# links_v40.net
KiCad netlist of a schematic drawn in EAGLE
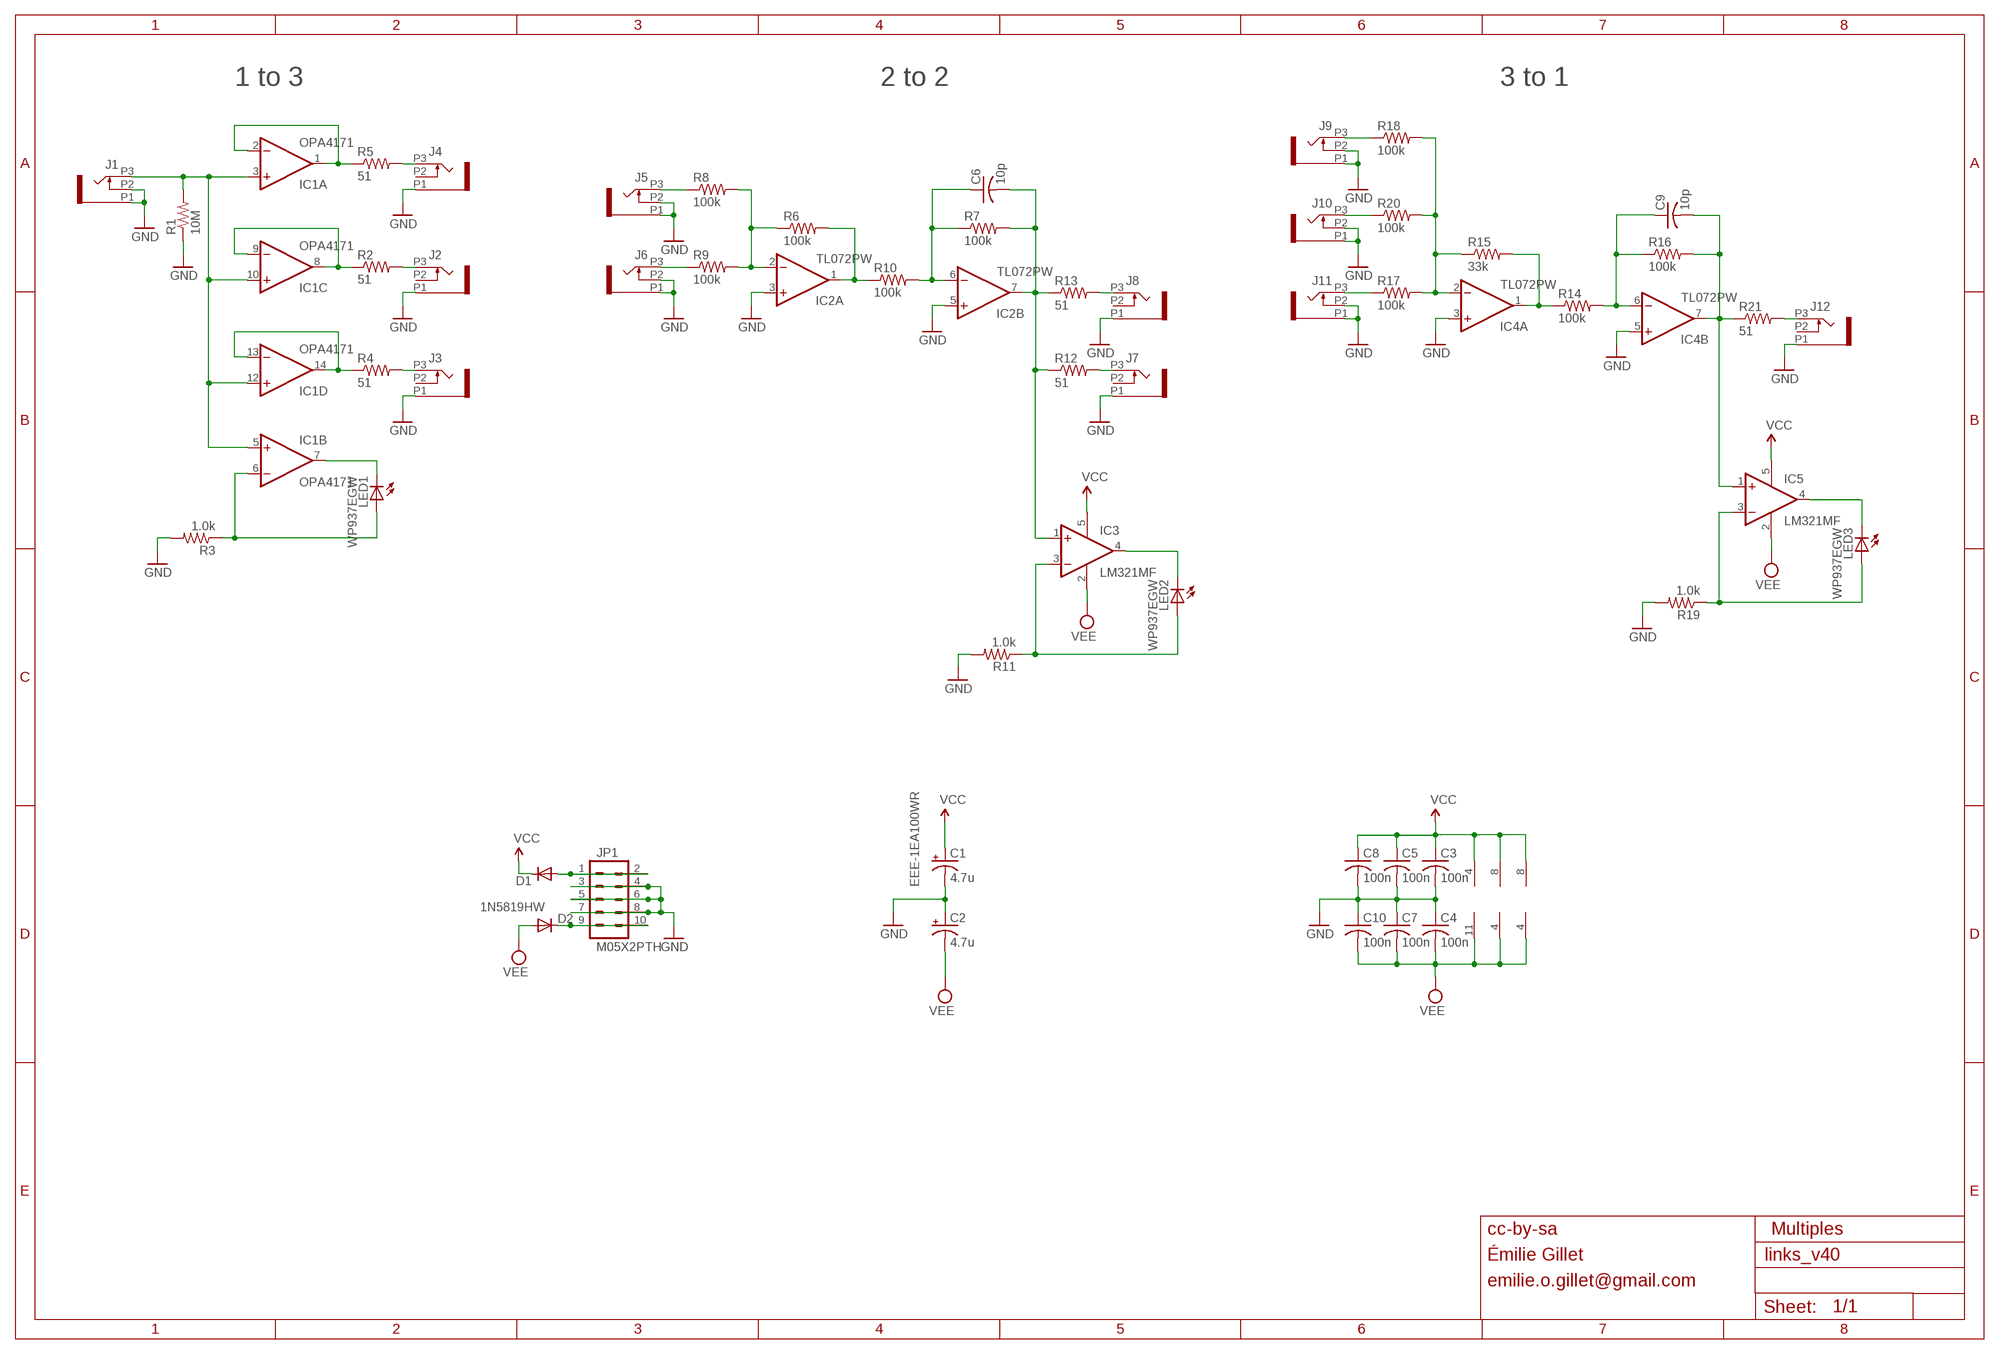
[diagram p0: schematic, sheet 1]

(export (version "E")
  (design (tool "Eeschema 10.0.6"))
  (components
    (comp (ref "C1")
      (value "4.7u")
      (footprint "eagle-import:PANASONIC_A")
      (libsource (lib "eagle-import") (part "CPOL-USA"))
    )
    (comp (ref "C2")
      (value "4.7u")
      (footprint "eagle-import:PANASONIC_A")
      (libsource (lib "eagle-import") (part "CPOL-USA"))
    )
    (comp (ref "C3")
      (value "100n")
      (footprint "eagle-import:C0603")
      (libsource (lib "eagle-import") (part "C-USC0603"))
    )
    (comp (ref "C4")
      (value "100n")
      (footprint "eagle-import:C0603")
      (libsource (lib "eagle-import") (part "C-USC0603"))
    )
    (comp (ref "C5")
      (value "100n")
      (footprint "eagle-import:C0603")
      (libsource (lib "eagle-import") (part "C-USC0603"))
    )
    (comp (ref "C6")
      (value "10p")
      (footprint "eagle-import:C0603")
      (libsource (lib "eagle-import") (part "C-USC0603"))
    )
    (comp (ref "C7")
      (value "100n")
      (footprint "eagle-import:C0603")
      (libsource (lib "eagle-import") (part "C-USC0603"))
    )
    (comp (ref "C8")
      (value "100n")
      (footprint "eagle-import:C0603")
      (libsource (lib "eagle-import") (part "C-USC0603"))
    )
    (comp (ref "C9")
      (value "10p")
      (footprint "eagle-import:C0603")
      (libsource (lib "eagle-import") (part "C-USC0603"))
    )
    (comp (ref "C10")
      (value "100n")
      (footprint "eagle-import:C0603")
      (libsource (lib "eagle-import") (part "C-USC0603"))
    )
    (comp (ref "D1")
      (value "1N5819HW")
      (footprint "eagle-import:SOD123")
      (libsource (lib "eagle-import") (part "DIODE-SOD123"))
    )
    (comp (ref "D2")
      (value "1N5819HW")
      (footprint "eagle-import:SOD123")
      (libsource (lib "eagle-import") (part "DIODE-SOD123"))
    )
    (comp (ref "IC1")
      (value "OPA4171")
      (footprint "eagle-import:TSSOP14")
      (libsource (lib "eagle-import") (part "TL074PW"))
    )
    (comp (ref "IC2")
      (value "TL072PW")
      (footprint "eagle-import:TSSOP8")
      (libsource (lib "eagle-import") (part "TL072PW"))
    )
    (comp (ref "IC3")
      (value "LM321MF")
      (footprint "eagle-import:SOT23-5")
      (libsource (lib "eagle-import") (part "LM321?MF"))
    )
    (comp (ref "IC4")
      (value "TL072PW")
      (footprint "eagle-import:TSSOP8")
      (libsource (lib "eagle-import") (part "TL072PW"))
    )
    (comp (ref "IC5")
      (value "LM321MF")
      (footprint "eagle-import:SOT23-5")
      (libsource (lib "eagle-import") (part "LM321?MF"))
    )
    (comp (ref "J1")
      (value "PJ301_THONKICONN6")
      (footprint "eagle-import:WQP_PJ_301M6")
      (libsource (lib "eagle-import") (part "PJ301_THONKICONN6"))
    )
    (comp (ref "J2")
      (value "PJ301_THONKICONN6")
      (footprint "eagle-import:WQP_PJ_301M6")
      (libsource (lib "eagle-import") (part "PJ301_THONKICONN6"))
    )
    (comp (ref "J3")
      (value "PJ301_THONKICONN6")
      (footprint "eagle-import:WQP_PJ_301M6")
      (libsource (lib "eagle-import") (part "PJ301_THONKICONN6"))
    )
    (comp (ref "J4")
      (value "PJ301_THONKICONN6")
      (footprint "eagle-import:WQP_PJ_301M6")
      (libsource (lib "eagle-import") (part "PJ301_THONKICONN6"))
    )
    (comp (ref "J5")
      (value "PJ301_THONKICONN6")
      (footprint "eagle-import:WQP_PJ_301M6")
      (libsource (lib "eagle-import") (part "PJ301_THONKICONN6"))
    )
    (comp (ref "J6")
      (value "PJ301_THONKICONN6")
      (footprint "eagle-import:WQP_PJ_301M6")
      (libsource (lib "eagle-import") (part "PJ301_THONKICONN6"))
    )
    (comp (ref "J7")
      (value "PJ301_THONKICONN6")
      (footprint "eagle-import:WQP_PJ_301M6")
      (libsource (lib "eagle-import") (part "PJ301_THONKICONN6"))
    )
    (comp (ref "J8")
      (value "PJ301_THONKICONN6")
      (footprint "eagle-import:WQP_PJ_301M6")
      (libsource (lib "eagle-import") (part "PJ301_THONKICONN6"))
    )
    (comp (ref "J9")
      (value "PJ301_THONKICONN6")
      (footprint "eagle-import:WQP_PJ_301M6")
      (libsource (lib "eagle-import") (part "PJ301_THONKICONN6"))
    )
    (comp (ref "J10")
      (value "PJ301_THONKICONN6")
      (footprint "eagle-import:WQP_PJ_301M6")
      (libsource (lib "eagle-import") (part "PJ301_THONKICONN6"))
    )
    (comp (ref "J11")
      (value "PJ301_THONKICONN6")
      (footprint "eagle-import:WQP_PJ_301M6")
      (libsource (lib "eagle-import") (part "PJ301_THONKICONN6"))
    )
    (comp (ref "J12")
      (value "PJ301_THONKICONN6")
      (footprint "eagle-import:WQP_PJ_301M6")
      (libsource (lib "eagle-import") (part "PJ301_THONKICONN6"))
    )
    (comp (ref "JP1")
      (value "M05X2PTH")
      (footprint "eagle-import:AVR_ICSP")
      (libsource (lib "eagle-import") (part "M05X2PTH"))
    )
    (comp (ref "LED1")
      (value "WP937EGW")
      (footprint "eagle-import:LED3MM")
      (libsource (lib "eagle-import") (part "LED3MM"))
    )
    (comp (ref "LED2")
      (value "WP937EGW")
      (footprint "eagle-import:LED3MM")
      (libsource (lib "eagle-import") (part "LED3MM"))
    )
    (comp (ref "LED3")
      (value "WP937EGW")
      (footprint "eagle-import:LED3MM")
      (libsource (lib "eagle-import") (part "LED3MM"))
    )
    (comp (ref "R1")
      (value "10M")
      (footprint "eagle-import:R0603")
      (libsource (lib "eagle-import") (part "R-US_R0603"))
    )
    (comp (ref "R2")
      (value "51")
      (footprint "eagle-import:R0603")
      (libsource (lib "eagle-import") (part "R-US_R0603"))
    )
    (comp (ref "R3")
      (value "1.0k")
      (footprint "eagle-import:R0603")
      (libsource (lib "eagle-import") (part "R-US_R0603"))
    )
    (comp (ref "R4")
      (value "51")
      (footprint "eagle-import:R0603")
      (libsource (lib "eagle-import") (part "R-US_R0603"))
    )
    (comp (ref "R5")
      (value "51")
      (footprint "eagle-import:R0603")
      (libsource (lib "eagle-import") (part "R-US_R0603"))
    )
    (comp (ref "R6")
      (value "100k")
      (footprint "eagle-import:R0603")
      (libsource (lib "eagle-import") (part "R-US_R0603"))
    )
    (comp (ref "R7")
      (value "100k")
      (footprint "eagle-import:R0603")
      (libsource (lib "eagle-import") (part "R-US_R0603"))
    )
    (comp (ref "R8")
      (value "100k")
      (footprint "eagle-import:R0603")
      (libsource (lib "eagle-import") (part "R-US_R0603"))
    )
    (comp (ref "R9")
      (value "100k")
      (footprint "eagle-import:R0603")
      (libsource (lib "eagle-import") (part "R-US_R0603"))
    )
    (comp (ref "R10")
      (value "100k")
      (footprint "eagle-import:R0603")
      (libsource (lib "eagle-import") (part "R-US_R0603"))
    )
    (comp (ref "R11")
      (value "1.0k")
      (footprint "eagle-import:R0603")
      (libsource (lib "eagle-import") (part "R-US_R0603"))
    )
    (comp (ref "R12")
      (value "51")
      (footprint "eagle-import:R0603")
      (libsource (lib "eagle-import") (part "R-US_R0603"))
    )
    (comp (ref "R13")
      (value "51")
      (footprint "eagle-import:R0603")
      (libsource (lib "eagle-import") (part "R-US_R0603"))
    )
    (comp (ref "R14")
      (value "100k")
      (footprint "eagle-import:R0603")
      (libsource (lib "eagle-import") (part "R-US_R0603"))
    )
    (comp (ref "R15")
      (value "33k")
      (footprint "eagle-import:R0603")
      (libsource (lib "eagle-import") (part "R-US_R0603"))
    )
    (comp (ref "R16")
      (value "100k")
      (footprint "eagle-import:R0603")
      (libsource (lib "eagle-import") (part "R-US_R0603"))
    )
    (comp (ref "R17")
      (value "100k")
      (footprint "eagle-import:R0603")
      (libsource (lib "eagle-import") (part "R-US_R0603"))
    )
    (comp (ref "R18")
      (value "100k")
      (footprint "eagle-import:R0603")
      (libsource (lib "eagle-import") (part "R-US_R0603"))
    )
    (comp (ref "R19")
      (value "1.0k")
      (footprint "eagle-import:R0603")
      (libsource (lib "eagle-import") (part "R-US_R0603"))
    )
    (comp (ref "R20")
      (value "100k")
      (footprint "eagle-import:R0603")
      (libsource (lib "eagle-import") (part "R-US_R0603"))
    )
    (comp (ref "R21")
      (value "51")
      (footprint "eagle-import:R0603")
      (libsource (lib "eagle-import") (part "R-US_R0603"))
    )
  )
  (nets
    (net (code "1") (name "GND") (class "Default")
      (node (ref "C1") (pin "-") (pinfunction "-_-") (pintype "passive"))
      (node (ref "C10") (pin "1") (pinfunction "1_1") (pintype "passive"))
      (node (ref "C2") (pin "+") (pinfunction "+_+") (pintype "passive"))
      (node (ref "C3") (pin "2") (pinfunction "2_2") (pintype "passive"))
      (node (ref "C4") (pin "1") (pinfunction "1_1") (pintype "passive"))
      (node (ref "C5") (pin "2") (pinfunction "2_2") (pintype "passive"))
      (node (ref "C7") (pin "1") (pinfunction "1_1") (pintype "passive"))
      (node (ref "C8") (pin "2") (pinfunction "2_2") (pintype "passive"))
      (node (ref "IC2") (pin "3") (pinfunction "+IN_3") (pintype "input"))
      (node (ref "IC2") (pin "5") (pinfunction "+IN_5") (pintype "input"))
      (node (ref "IC4") (pin "3") (pinfunction "+IN_3") (pintype "input"))
      (node (ref "IC4") (pin "5") (pinfunction "+IN_5") (pintype "input"))
      (node (ref "J1") (pin "P1") (pinfunction "1_P1") (pintype "passive"))
      (node (ref "J1") (pin "P2") (pinfunction "2_P2") (pintype "passive"))
      (node (ref "J10") (pin "P1") (pinfunction "1_P1") (pintype "passive"))
      (node (ref "J10") (pin "P2") (pinfunction "2_P2") (pintype "passive"))
      (node (ref "J11") (pin "P1") (pinfunction "1_P1") (pintype "passive"))
      (node (ref "J11") (pin "P2") (pinfunction "2_P2") (pintype "passive"))
      (node (ref "J12") (pin "P1") (pinfunction "1_P1") (pintype "passive"))
      (node (ref "J2") (pin "P1") (pinfunction "1_P1") (pintype "passive"))
      (node (ref "J3") (pin "P1") (pinfunction "1_P1") (pintype "passive"))
      (node (ref "J4") (pin "P1") (pinfunction "1_P1") (pintype "passive"))
      (node (ref "J5") (pin "P1") (pinfunction "1_P1") (pintype "passive"))
      (node (ref "J5") (pin "P2") (pinfunction "2_P2") (pintype "passive"))
      (node (ref "J6") (pin "P1") (pinfunction "1_P1") (pintype "passive"))
      (node (ref "J6") (pin "P2") (pinfunction "2_P2") (pintype "passive"))
      (node (ref "J7") (pin "P1") (pinfunction "1_P1") (pintype "passive"))
      (node (ref "J8") (pin "P1") (pinfunction "1_P1") (pintype "passive"))
      (node (ref "J9") (pin "P1") (pinfunction "1_P1") (pintype "passive"))
      (node (ref "J9") (pin "P2") (pinfunction "2_P2") (pintype "passive"))
      (node (ref "JP1") (pin "3") (pinfunction "3_3") (pintype "passive"))
      (node (ref "JP1") (pin "4") (pinfunction "4_4") (pintype "passive"))
      (node (ref "JP1") (pin "5") (pinfunction "5_5") (pintype "passive"))
      (node (ref "JP1") (pin "6") (pinfunction "6_6") (pintype "passive"))
      (node (ref "JP1") (pin "7") (pinfunction "7_7") (pintype "passive"))
      (node (ref "JP1") (pin "8") (pinfunction "8_8") (pintype "passive"))
      (node (ref "R1") (pin "1") (pinfunction "1_1") (pintype "passive"))
      (node (ref "R11") (pin "2") (pinfunction "2_2") (pintype "passive"))
      (node (ref "R19") (pin "2") (pinfunction "2_2") (pintype "passive"))
      (node (ref "R3") (pin "2") (pinfunction "2_2") (pintype "passive"))
    )
    (net (code "2") (name "Net-(D1-PadA)") (class "Default")
      (node (ref "D1") (pin "A") (pinfunction "A_A") (pintype "passive"))
      (node (ref "JP1") (pin "1") (pinfunction "1_1") (pintype "passive"))
      (node (ref "JP1") (pin "2") (pinfunction "2_2") (pintype "passive"))
    )
    (net (code "3") (name "Net-(D2-PadC)") (class "Default")
      (node (ref "D2") (pin "C") (pinfunction "C_C") (pintype "passive"))
      (node (ref "JP1") (pin "10") (pinfunction "10_10") (pintype "passive"))
      (node (ref "JP1") (pin "9") (pinfunction "9_9") (pintype "passive"))
    )
    (net (code "4") (name "Net-(IC1A-+IN)") (class "Default")
      (node (ref "IC1") (pin "10") (pinfunction "+IN_10") (pintype "input"))
      (node (ref "IC1") (pin "12") (pinfunction "+IN_12") (pintype "input"))
      (node (ref "IC1") (pin "3") (pinfunction "+IN_3") (pintype "input"))
      (node (ref "IC1") (pin "5") (pinfunction "+IN_5") (pintype "input"))
      (node (ref "J1") (pin "P3") (pinfunction "3_P3") (pintype "passive"))
      (node (ref "R1") (pin "2") (pinfunction "2_2") (pintype "passive"))
    )
    (net (code "5") (name "Net-(IC1A--IN)") (class "Default")
      (node (ref "IC1") (pin "1") (pinfunction "OUT_1") (pintype "output"))
      (node (ref "IC1") (pin "2") (pinfunction "-IN_2") (pintype "input"))
      (node (ref "R5") (pin "1") (pinfunction "1_1") (pintype "passive"))
    )
    (net (code "6") (name "Net-(IC1B--IN)") (class "Default")
      (node (ref "IC1") (pin "6") (pinfunction "-IN_6") (pintype "input"))
      (node (ref "LED1") (pin "A") (pinfunction "A_A") (pintype "passive"))
      (node (ref "R3") (pin "1") (pinfunction "1_1") (pintype "passive"))
    )
    (net (code "7") (name "Net-(IC1B-OUT)") (class "Default")
      (node (ref "IC1") (pin "7") (pinfunction "OUT_7") (pintype "output"))
      (node (ref "LED1") (pin "K") (pinfunction "C_K") (pintype "passive"))
    )
    (net (code "8") (name "Net-(IC1C--IN)") (class "Default")
      (node (ref "IC1") (pin "8") (pinfunction "OUT_8") (pintype "output"))
      (node (ref "IC1") (pin "9") (pinfunction "-IN_9") (pintype "input"))
      (node (ref "R2") (pin "1") (pinfunction "1_1") (pintype "passive"))
    )
    (net (code "9") (name "Net-(IC1D--IN)") (class "Default")
      (node (ref "IC1") (pin "13") (pinfunction "-IN_13") (pintype "input"))
      (node (ref "IC1") (pin "14") (pinfunction "OUT_14") (pintype "output"))
      (node (ref "R4") (pin "1") (pinfunction "1_1") (pintype "passive"))
    )
    (net (code "10") (name "Net-(IC2A--IN)") (class "Default")
      (node (ref "IC2") (pin "2") (pinfunction "-IN_2") (pintype "input"))
      (node (ref "R6") (pin "1") (pinfunction "1_1") (pintype "passive"))
      (node (ref "R8") (pin "2") (pinfunction "2_2") (pintype "passive"))
      (node (ref "R9") (pin "2") (pinfunction "2_2") (pintype "passive"))
    )
    (net (code "11") (name "Net-(IC2A-OUT)") (class "Default")
      (node (ref "IC2") (pin "1") (pinfunction "OUT_1") (pintype "output"))
      (node (ref "R10") (pin "1") (pinfunction "1_1") (pintype "passive"))
      (node (ref "R6") (pin "2") (pinfunction "2_2") (pintype "passive"))
    )
    (net (code "12") (name "Net-(IC2B--IN)") (class "Default")
      (node (ref "C6") (pin "1") (pinfunction "1_1") (pintype "passive"))
      (node (ref "IC2") (pin "6") (pinfunction "-IN_6") (pintype "input"))
      (node (ref "R10") (pin "2") (pinfunction "2_2") (pintype "passive"))
      (node (ref "R7") (pin "1") (pinfunction "1_1") (pintype "passive"))
    )
    (net (code "13") (name "Net-(IC2B-OUT)") (class "Default")
      (node (ref "C6") (pin "2") (pinfunction "2_2") (pintype "passive"))
      (node (ref "IC2") (pin "7") (pinfunction "OUT_7") (pintype "output"))
      (node (ref "IC3") (pin "1") (pinfunction "+IN_1") (pintype "input"))
      (node (ref "R12") (pin "1") (pinfunction "1_1") (pintype "passive"))
      (node (ref "R13") (pin "1") (pinfunction "1_1") (pintype "passive"))
      (node (ref "R7") (pin "2") (pinfunction "2_2") (pintype "passive"))
    )
    (net (code "14") (name "Net-(IC3--IN)") (class "Default")
      (node (ref "IC3") (pin "3") (pinfunction "-IN_3") (pintype "input"))
      (node (ref "LED2") (pin "A") (pinfunction "A_A") (pintype "passive"))
      (node (ref "R11") (pin "1") (pinfunction "1_1") (pintype "passive"))
    )
    (net (code "15") (name "Net-(IC3-OUT)") (class "Default")
      (node (ref "IC3") (pin "4") (pinfunction "OUT_4") (pintype "output"))
      (node (ref "LED2") (pin "K") (pinfunction "C_K") (pintype "passive"))
    )
    (net (code "16") (name "Net-(IC4A--IN)") (class "Default")
      (node (ref "IC4") (pin "2") (pinfunction "-IN_2") (pintype "input"))
      (node (ref "R15") (pin "1") (pinfunction "1_1") (pintype "passive"))
      (node (ref "R17") (pin "2") (pinfunction "2_2") (pintype "passive"))
      (node (ref "R18") (pin "2") (pinfunction "2_2") (pintype "passive"))
      (node (ref "R20") (pin "2") (pinfunction "2_2") (pintype "passive"))
    )
    (net (code "17") (name "Net-(IC4A-OUT)") (class "Default")
      (node (ref "IC4") (pin "1") (pinfunction "OUT_1") (pintype "output"))
      (node (ref "R14") (pin "1") (pinfunction "1_1") (pintype "passive"))
      (node (ref "R15") (pin "2") (pinfunction "2_2") (pintype "passive"))
    )
    (net (code "18") (name "Net-(IC4B--IN)") (class "Default")
      (node (ref "C9") (pin "1") (pinfunction "1_1") (pintype "passive"))
      (node (ref "IC4") (pin "6") (pinfunction "-IN_6") (pintype "input"))
      (node (ref "R14") (pin "2") (pinfunction "2_2") (pintype "passive"))
      (node (ref "R16") (pin "1") (pinfunction "1_1") (pintype "passive"))
    )
    (net (code "19") (name "Net-(IC4B-OUT)") (class "Default")
      (node (ref "C9") (pin "2") (pinfunction "2_2") (pintype "passive"))
      (node (ref "IC4") (pin "7") (pinfunction "OUT_7") (pintype "output"))
      (node (ref "IC5") (pin "1") (pinfunction "+IN_1") (pintype "input"))
      (node (ref "R16") (pin "2") (pinfunction "2_2") (pintype "passive"))
      (node (ref "R21") (pin "1") (pinfunction "1_1") (pintype "passive"))
    )
    (net (code "20") (name "Net-(IC5--IN)") (class "Default")
      (node (ref "IC5") (pin "3") (pinfunction "-IN_3") (pintype "input"))
      (node (ref "LED3") (pin "A") (pinfunction "A_A") (pintype "passive"))
      (node (ref "R19") (pin "1") (pinfunction "1_1") (pintype "passive"))
    )
    (net (code "21") (name "Net-(IC5-OUT)") (class "Default")
      (node (ref "IC5") (pin "4") (pinfunction "OUT_4") (pintype "output"))
      (node (ref "LED3") (pin "K") (pinfunction "C_K") (pintype "passive"))
    )
    (net (code "22") (name "Net-(J2-3)") (class "Default")
      (node (ref "J2") (pin "P3") (pinfunction "3_P3") (pintype "passive"))
      (node (ref "R2") (pin "2") (pinfunction "2_2") (pintype "passive"))
    )
    (net (code "23") (name "Net-(J3-3)") (class "Default")
      (node (ref "J3") (pin "P3") (pinfunction "3_P3") (pintype "passive"))
      (node (ref "R4") (pin "2") (pinfunction "2_2") (pintype "passive"))
    )
    (net (code "24") (name "Net-(J4-3)") (class "Default")
      (node (ref "J4") (pin "P3") (pinfunction "3_P3") (pintype "passive"))
      (node (ref "R5") (pin "2") (pinfunction "2_2") (pintype "passive"))
    )
    (net (code "25") (name "Net-(J5-3)") (class "Default")
      (node (ref "J5") (pin "P3") (pinfunction "3_P3") (pintype "passive"))
      (node (ref "R8") (pin "1") (pinfunction "1_1") (pintype "passive"))
    )
    (net (code "26") (name "Net-(J6-3)") (class "Default")
      (node (ref "J6") (pin "P3") (pinfunction "3_P3") (pintype "passive"))
      (node (ref "R9") (pin "1") (pinfunction "1_1") (pintype "passive"))
    )
    (net (code "27") (name "Net-(J7-3)") (class "Default")
      (node (ref "J7") (pin "P3") (pinfunction "3_P3") (pintype "passive"))
      (node (ref "R12") (pin "2") (pinfunction "2_2") (pintype "passive"))
    )
    (net (code "28") (name "Net-(J8-3)") (class "Default")
      (node (ref "J8") (pin "P3") (pinfunction "3_P3") (pintype "passive"))
      (node (ref "R13") (pin "2") (pinfunction "2_2") (pintype "passive"))
    )
    (net (code "29") (name "Net-(J9-3)") (class "Default")
      (node (ref "J9") (pin "P3") (pinfunction "3_P3") (pintype "passive"))
      (node (ref "R18") (pin "1") (pinfunction "1_1") (pintype "passive"))
    )
    (net (code "30") (name "Net-(J10-3)") (class "Default")
      (node (ref "J10") (pin "P3") (pinfunction "3_P3") (pintype "passive"))
      (node (ref "R20") (pin "1") (pinfunction "1_1") (pintype "passive"))
    )
    (net (code "31") (name "Net-(J11-3)") (class "Default")
      (node (ref "J11") (pin "P3") (pinfunction "3_P3") (pintype "passive"))
      (node (ref "R17") (pin "1") (pinfunction "1_1") (pintype "passive"))
    )
    (net (code "32") (name "Net-(J12-3)") (class "Default")
      (node (ref "J12") (pin "P3") (pinfunction "3_P3") (pintype "passive"))
      (node (ref "R21") (pin "2") (pinfunction "2_2") (pintype "passive"))
    )
    (net (code "33") (name "VCC") (class "Default")
      (node (ref "C1") (pin "+") (pinfunction "+_+") (pintype "passive"))
      (node (ref "C3") (pin "1") (pinfunction "1_1") (pintype "passive"))
      (node (ref "C5") (pin "1") (pinfunction "1_1") (pintype "passive"))
      (node (ref "C8") (pin "1") (pinfunction "1_1") (pintype "passive"))
      (node (ref "D1") (pin "C") (pinfunction "C_C") (pintype "passive"))
      (node (ref "IC1") (pin "4") (pinfunction "V+_4") (pintype "power_in"))
      (node (ref "IC2") (pin "8") (pinfunction "V+_8") (pintype "power_in"))
      (node (ref "IC3") (pin "5") (pinfunction "V+_5") (pintype "power_in"))
      (node (ref "IC4") (pin "8") (pinfunction "V+_8") (pintype "power_in"))
      (node (ref "IC5") (pin "5") (pinfunction "V+_5") (pintype "power_in"))
    )
    (net (code "34") (name "VEE") (class "Default")
      (node (ref "C10") (pin "2") (pinfunction "2_2") (pintype "passive"))
      (node (ref "C2") (pin "-") (pinfunction "-_-") (pintype "passive"))
      (node (ref "C4") (pin "2") (pinfunction "2_2") (pintype "passive"))
      (node (ref "C7") (pin "2") (pinfunction "2_2") (pintype "passive"))
      (node (ref "D2") (pin "A") (pinfunction "A_A") (pintype "passive"))
      (node (ref "IC1") (pin "11") (pinfunction "V-_11") (pintype "power_in"))
      (node (ref "IC2") (pin "4") (pinfunction "V-_4") (pintype "power_in"))
      (node (ref "IC3") (pin "2") (pinfunction "V-_2") (pintype "power_in"))
      (node (ref "IC4") (pin "4") (pinfunction "V-_4") (pintype "power_in"))
      (node (ref "IC5") (pin "2") (pinfunction "V-_2") (pintype "power_in"))
    )
    (net (code "35") (name "unconnected-(J2-2-PadP2)") (class "Default")
      (node (ref "J2") (pin "P2") (pinfunction "2_P2") (pintype "passive"))
    )
    (net (code "36") (name "unconnected-(J3-2-PadP2)") (class "Default")
      (node (ref "J3") (pin "P2") (pinfunction "2_P2") (pintype "passive"))
    )
    (net (code "37") (name "unconnected-(J4-2-PadP2)") (class "Default")
      (node (ref "J4") (pin "P2") (pinfunction "2_P2") (pintype "passive"))
    )
    (net (code "38") (name "unconnected-(J7-2-PadP2)") (class "Default")
      (node (ref "J7") (pin "P2") (pinfunction "2_P2") (pintype "passive"))
    )
    (net (code "39") (name "unconnected-(J8-2-PadP2)") (class "Default")
      (node (ref "J8") (pin "P2") (pinfunction "2_P2") (pintype "passive"))
    )
    (net (code "40") (name "unconnected-(J12-2-PadP2)") (class "Default")
      (node (ref "J12") (pin "P2") (pinfunction "2_P2") (pintype "passive"))
    )
  )
)
